# C64_Kernal_Switch.net
KiCad netlist of a schematic drawn in EAGLE
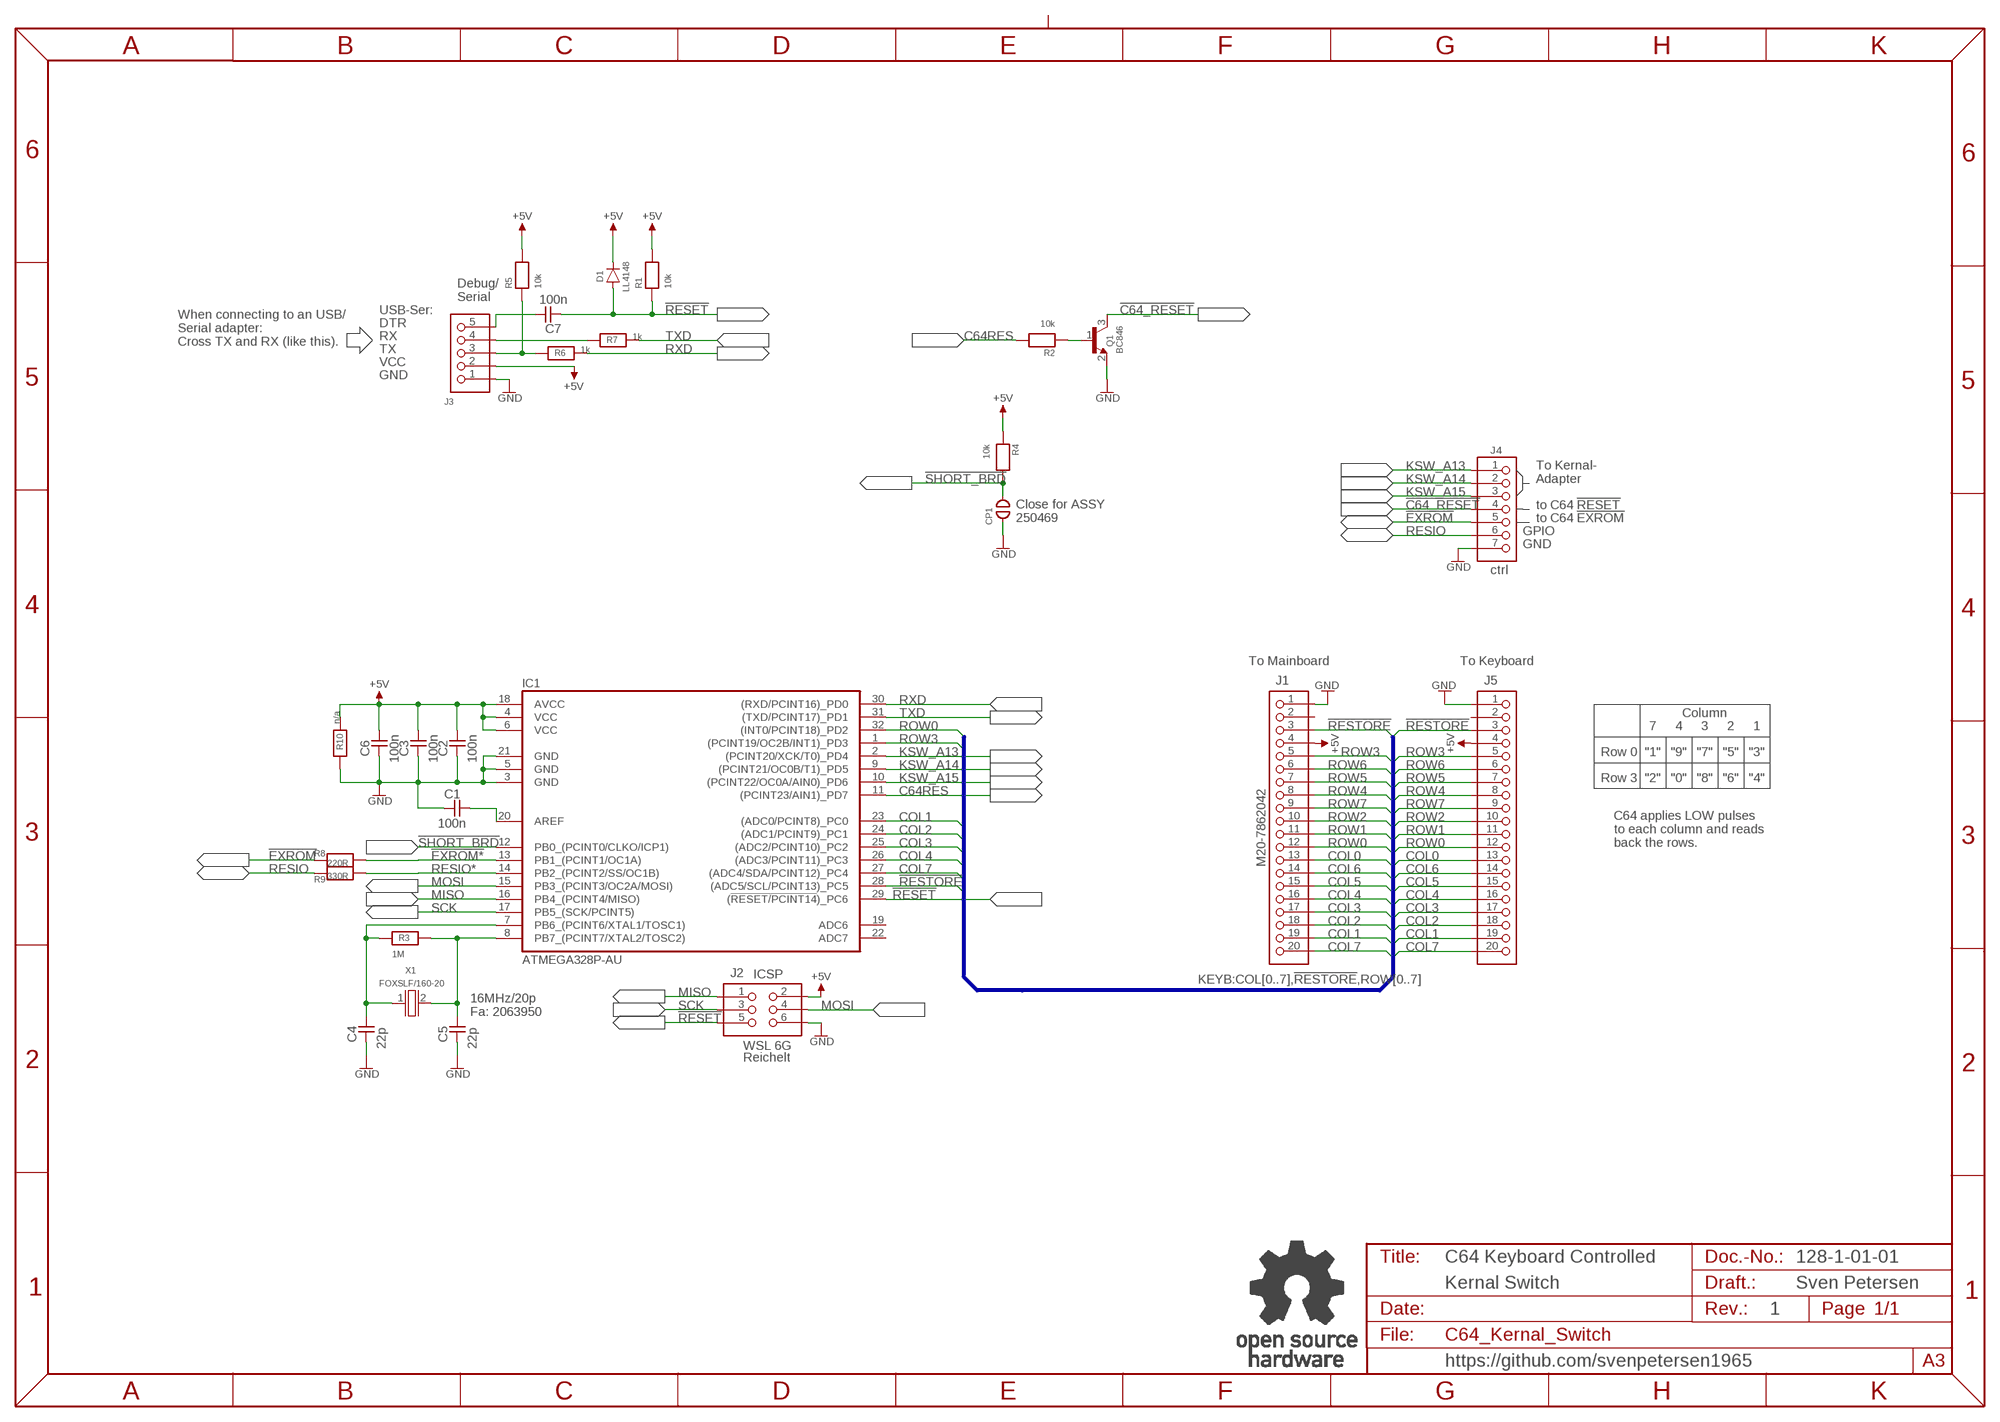
[diagram p0: schematic, sheet 1]

(export (version "E")
  (design (tool "Eeschema 10.0.6"))
  (components
    (comp (ref "C1")
      (value "100n")
      (footprint "eagle-import:0805")
      (libsource (lib "eagle-import") (part "C-0805"))
    )
    (comp (ref "C2")
      (value "100n")
      (footprint "eagle-import:0805")
      (libsource (lib "eagle-import") (part "C-0805"))
    )
    (comp (ref "C3")
      (value "100n")
      (footprint "eagle-import:0805")
      (libsource (lib "eagle-import") (part "C-0805"))
    )
    (comp (ref "C4")
      (value "22p")
      (footprint "eagle-import:0805")
      (libsource (lib "eagle-import") (part "C-0805"))
    )
    (comp (ref "C5")
      (value "22p")
      (footprint "eagle-import:0805")
      (libsource (lib "eagle-import") (part "C-0805"))
    )
    (comp (ref "C6")
      (value "100n")
      (footprint "eagle-import:0805")
      (libsource (lib "eagle-import") (part "C-0805"))
    )
    (comp (ref "C7")
      (value "100n")
      (footprint "eagle-import:0805")
      (libsource (lib "eagle-import") (part "C-0805"))
    )
    (comp (ref "CP1")
      (value "OPEN")
      (footprint "eagle-import:CP_OP")
      (libsource (lib "eagle-import") (part "OPEN"))
    )
    (comp (ref "D1")
      (value "LL4148")
      (footprint "eagle-import:SOD80C")
      (libsource (lib "eagle-import") (part "LL4148"))
    )
    (comp (ref "IC1")
      (value "ATMEGA328P-AU")
      (footprint "eagle-import:QFP80P900X900X120-32N")
      (fields (field (name "MPN") "ATMEGA328-AU"))
      (libsource (lib "eagle-import") (part "ATMEGA328-AU"))
    )
    (comp (ref "J1")
      (value "M20-7862042")
      (footprint "eagle-import:C64_KEYBOARD")
      (fields (field (name "SPICEPREFIX") "X"))
      (libsource (lib "eagle-import") (part "M20-7862042C64KB"))
    )
    (comp (ref "J2")
      (value "WSL 6G")
      (footprint "eagle-import:2X03WV")
      (libsource (lib "eagle-import") (part "2X03WV"))
    )
    (comp (ref "J3")
      (value "n/a")
      (footprint "eagle-import:1X05")
      (libsource (lib "eagle-import") (part "PINHD-1X5"))
    )
    (comp (ref "J4")
      (value "PINHD-1X7")
      (footprint "eagle-import:1X07")
      (libsource (lib "eagle-import") (part "PINHD-1X7"))
    )
    (comp (ref "J5")
      (value "PINHD-1X20")
      (footprint "eagle-import:1X20")
      (libsource (lib "eagle-import") (part "PINHD-1X20"))
    )
    (comp (ref "Q1")
      (value "BC846")
      (footprint "eagle-import:SOT23")
      (libsource (lib "eagle-import") (part "BC846"))
    )
    (comp (ref "R1")
      (value "10k")
      (footprint "eagle-import:0805")
      (libsource (lib "eagle-import") (part "R-0805"))
    )
    (comp (ref "R2")
      (value "10k")
      (footprint "eagle-import:0805")
      (libsource (lib "eagle-import") (part "R-0805"))
    )
    (comp (ref "R3")
      (value "1M")
      (footprint "eagle-import:0805")
      (libsource (lib "eagle-import") (part "R-0805"))
    )
    (comp (ref "R4")
      (value "10k")
      (footprint "eagle-import:0805")
      (libsource (lib "eagle-import") (part "R-0805"))
    )
    (comp (ref "R5")
      (value "10k")
      (footprint "eagle-import:0805")
      (libsource (lib "eagle-import") (part "R-0805"))
    )
    (comp (ref "R6")
      (value "1k")
      (footprint "eagle-import:0805")
      (libsource (lib "eagle-import") (part "R-0805"))
    )
    (comp (ref "R7")
      (value "1k")
      (footprint "eagle-import:0805")
      (libsource (lib "eagle-import") (part "R-0805"))
    )
    (comp (ref "R8")
      (value "220R")
      (footprint "eagle-import:0805")
      (libsource (lib "eagle-import") (part "R-0805"))
    )
    (comp (ref "R9")
      (value "330R")
      (footprint "eagle-import:0805")
      (libsource (lib "eagle-import") (part "R-0805"))
    )
    (comp (ref "R10")
      (value "n/a")
      (footprint "eagle-import:0805")
      (libsource (lib "eagle-import") (part "R-0805"))
    )
    (comp (ref "U$55")
      (value "OPEN_SOURCE_HW")
      (footprint "eagle-import:OPENHW")
      (libsource (lib "eagle-import") (part "OPEN_SOURCE_HW"))
    )
    (comp (ref "X1")
      (value "FOXSLF/160-20")
      (footprint "eagle-import:HC49SLF")
      (libsource (lib "eagle-import") (part "HC49SLF"))
    )
  )
  (nets
    (net (code "1") (name "+5V") (class "Default")
      (node (ref "C2") (pin "2") (pinfunction "2_2") (pintype "passive"))
      (node (ref "C3") (pin "2") (pinfunction "2_2") (pintype "passive"))
      (node (ref "C6") (pin "2") (pinfunction "2_2") (pintype "passive"))
      (node (ref "D1") (pin "K") (pinfunction "K_K") (pintype "passive"))
      (node (ref "IC1") (pin "18") (pinfunction "AVCC_18") (pintype "power_in"))
      (node (ref "IC1") (pin "4") (pinfunction "VCC_4") (pintype "power_in"))
      (node (ref "IC1") (pin "6") (pinfunction "VCC_6") (pintype "power_in"))
      (node (ref "J1") (pin "4") (pinfunction "4_4") (pintype "bidirectional"))
      (node (ref "J2") (pin "2") (pinfunction "2_2") (pintype "passive"))
      (node (ref "J3") (pin "2") (pinfunction "2_2") (pintype "passive"))
      (node (ref "J5") (pin "4") (pinfunction "4_4") (pintype "passive"))
      (node (ref "R1") (pin "2") (pinfunction "2_2") (pintype "passive"))
      (node (ref "R10") (pin "2") (pinfunction "2_2") (pintype "passive"))
      (node (ref "R4") (pin "1") (pinfunction "1_1") (pintype "passive"))
      (node (ref "R5") (pin "2") (pinfunction "2_2") (pintype "passive"))
    )
    (net (code "2") (name "/C64RES") (class "Default")
      (node (ref "IC1") (pin "11") (pinfunction "(PCINT23/AIN1)_PD7_11") (pintype "bidirectional"))
      (node (ref "R2") (pin "2") (pinfunction "2_2") (pintype "passive"))
    )
    (net (code "3") (name "/COL0") (class "Default")
      (node (ref "J1") (pin "13") (pinfunction "13_13") (pintype "bidirectional"))
      (node (ref "J5") (pin "13") (pinfunction "13_13") (pintype "passive"))
    )
    (net (code "4") (name "/COL1") (class "Default")
      (node (ref "IC1") (pin "23") (pinfunction "(ADC0/PCINT8)_PC0_23") (pintype "bidirectional"))
      (node (ref "J1") (pin "19") (pinfunction "19_19") (pintype "bidirectional"))
      (node (ref "J5") (pin "19") (pinfunction "19_19") (pintype "passive"))
    )
    (net (code "5") (name "/COL2") (class "Default")
      (node (ref "IC1") (pin "24") (pinfunction "(ADC1/PCINT9)_PC1_24") (pintype "bidirectional"))
      (node (ref "J1") (pin "18") (pinfunction "18_18") (pintype "bidirectional"))
      (node (ref "J5") (pin "18") (pinfunction "18_18") (pintype "passive"))
    )
    (net (code "6") (name "/COL3") (class "Default")
      (node (ref "IC1") (pin "25") (pinfunction "(ADC2/PCINT10)_PC2_25") (pintype "bidirectional"))
      (node (ref "J1") (pin "17") (pinfunction "17_17") (pintype "bidirectional"))
      (node (ref "J5") (pin "17") (pinfunction "17_17") (pintype "passive"))
    )
    (net (code "7") (name "/COL4") (class "Default")
      (node (ref "IC1") (pin "26") (pinfunction "(ADC3/PCINT11)_PC3_26") (pintype "bidirectional"))
      (node (ref "J1") (pin "16") (pinfunction "16_16") (pintype "bidirectional"))
      (node (ref "J5") (pin "16") (pinfunction "16_16") (pintype "passive"))
    )
    (net (code "8") (name "/COL5") (class "Default")
      (node (ref "J1") (pin "15") (pinfunction "15_15") (pintype "bidirectional"))
      (node (ref "J5") (pin "15") (pinfunction "15_15") (pintype "passive"))
    )
    (net (code "9") (name "/COL6") (class "Default")
      (node (ref "J1") (pin "14") (pinfunction "14_14") (pintype "bidirectional"))
      (node (ref "J5") (pin "14") (pinfunction "14_14") (pintype "passive"))
    )
    (net (code "10") (name "/COL7") (class "Default")
      (node (ref "IC1") (pin "27") (pinfunction "(ADC4/SDA/PCINT12)_PC4_27") (pintype "bidirectional"))
      (node (ref "J1") (pin "20") (pinfunction "20_20") (pintype "bidirectional"))
      (node (ref "J5") (pin "20") (pinfunction "20_20") (pintype "passive"))
    )
    (net (code "11") (name "/KSW_A13") (class "Default")
      (node (ref "IC1") (pin "2") (pinfunction "(PCINT20/XCK/T0)_PD4_2") (pintype "bidirectional"))
      (node (ref "J4") (pin "1") (pinfunction "1_1") (pintype "passive"))
    )
    (net (code "12") (name "/KSW_A14") (class "Default")
      (node (ref "IC1") (pin "9") (pinfunction "(PCINT21/OC0B/T1)_PD5_9") (pintype "bidirectional"))
      (node (ref "J4") (pin "2") (pinfunction "2_2") (pintype "passive"))
    )
    (net (code "13") (name "/KSW_A15") (class "Default")
      (node (ref "IC1") (pin "10") (pinfunction "(PCINT22/OC0A/AIN0)_PD6_10") (pintype "bidirectional"))
      (node (ref "J4") (pin "3") (pinfunction "3_3") (pintype "passive"))
    )
    (net (code "14") (name "/MISO") (class "Default")
      (node (ref "IC1") (pin "16") (pinfunction "PB4_(PCINT4/MISO)_16") (pintype "bidirectional"))
      (node (ref "J2") (pin "1") (pinfunction "1_1") (pintype "passive"))
    )
    (net (code "15") (name "/MOSI") (class "Default")
      (node (ref "IC1") (pin "15") (pinfunction "PB3_(PCINT3/OC2A/MOSI)_15") (pintype "bidirectional"))
      (node (ref "J2") (pin "4") (pinfunction "4_4") (pintype "passive"))
    )
    (net (code "16") (name "/RESIO") (class "Default")
      (node (ref "J4") (pin "6") (pinfunction "6_6") (pintype "passive"))
      (node (ref "R9") (pin "1") (pinfunction "1_1") (pintype "passive"))
    )
    (net (code "17") (name "/RESIO*") (class "Default")
      (node (ref "IC1") (pin "14") (pinfunction "PB2_(PCINT2/SS/OC1B)_14") (pintype "bidirectional"))
      (node (ref "R9") (pin "2") (pinfunction "2_2") (pintype "passive"))
    )
    (net (code "18") (name "/ROW0") (class "Default")
      (node (ref "IC1") (pin "32") (pinfunction "(INT0/PCINT18)_PD2_32") (pintype "bidirectional"))
      (node (ref "J1") (pin "12") (pinfunction "12_12") (pintype "bidirectional"))
      (node (ref "J5") (pin "12") (pinfunction "12_12") (pintype "passive"))
    )
    (net (code "19") (name "/ROW1") (class "Default")
      (node (ref "J1") (pin "11") (pinfunction "11_11") (pintype "bidirectional"))
      (node (ref "J5") (pin "11") (pinfunction "11_11") (pintype "passive"))
    )
    (net (code "20") (name "/ROW2") (class "Default")
      (node (ref "J1") (pin "10") (pinfunction "10_10") (pintype "bidirectional"))
      (node (ref "J5") (pin "10") (pinfunction "10_10") (pintype "passive"))
    )
    (net (code "21") (name "/ROW3") (class "Default")
      (node (ref "IC1") (pin "1") (pinfunction "(PCINT19/OC2B/INT1)_PD3_1") (pintype "bidirectional"))
      (node (ref "J1") (pin "5") (pinfunction "5_5") (pintype "bidirectional"))
      (node (ref "J5") (pin "5") (pinfunction "5_5") (pintype "passive"))
    )
    (net (code "22") (name "/ROW4") (class "Default")
      (node (ref "J1") (pin "8") (pinfunction "8_8") (pintype "bidirectional"))
      (node (ref "J5") (pin "8") (pinfunction "8_8") (pintype "passive"))
    )
    (net (code "23") (name "/ROW5") (class "Default")
      (node (ref "J1") (pin "7") (pinfunction "7_7") (pintype "bidirectional"))
      (node (ref "J5") (pin "7") (pinfunction "7_7") (pintype "passive"))
    )
    (net (code "24") (name "/ROW6") (class "Default")
      (node (ref "J1") (pin "6") (pinfunction "6_6") (pintype "bidirectional"))
      (node (ref "J5") (pin "6") (pinfunction "6_6") (pintype "passive"))
    )
    (net (code "25") (name "/ROW7") (class "Default")
      (node (ref "J1") (pin "9") (pinfunction "9_9") (pintype "bidirectional"))
      (node (ref "J5") (pin "9") (pinfunction "9_9") (pintype "passive"))
    )
    (net (code "26") (name "/RXD") (class "Default")
      (node (ref "IC1") (pin "30") (pinfunction "(RXD/PCINT16)_PD0_30") (pintype "bidirectional"))
      (node (ref "R6") (pin "2") (pinfunction "2_2") (pintype "passive"))
    )
    (net (code "27") (name "/SCK") (class "Default")
      (node (ref "IC1") (pin "17") (pinfunction "PB5_(SCK/PCINT5)_17") (pintype "bidirectional"))
      (node (ref "J2") (pin "3") (pinfunction "3_3") (pintype "passive"))
    )
    (net (code "28") (name "/TXD") (class "Default")
      (node (ref "IC1") (pin "31") (pinfunction "(TXD/PCINT17)_PD1_31") (pintype "bidirectional"))
      (node (ref "R7") (pin "2") (pinfunction "2_2") (pintype "passive"))
    )
    (net (code "30") (name "/~{C64_RESET}") (class "Default")
      (node (ref "J4") (pin "4") (pinfunction "4_4") (pintype "passive"))
      (node (ref "Q1") (pin "3") (pinfunction "C_3") (pintype "passive"))
    )
    (net (code "31") (name "/~{EXROM*}") (class "Default")
      (node (ref "IC1") (pin "13") (pinfunction "PB1_(PCINT1/OC1A)_13") (pintype "bidirectional"))
      (node (ref "R8") (pin "2") (pinfunction "2_2") (pintype "passive"))
    )
    (net (code "32") (name "/~{EXROM}") (class "Default")
      (node (ref "J4") (pin "5") (pinfunction "5_5") (pintype "passive"))
      (node (ref "R8") (pin "1") (pinfunction "1_1") (pintype "passive"))
    )
    (net (code "33") (name "/~{RESET}") (class "Default")
      (node (ref "C7") (pin "1") (pinfunction "1_1") (pintype "passive"))
      (node (ref "D1") (pin "A") (pinfunction "A_A") (pintype "passive"))
      (node (ref "IC1") (pin "29") (pinfunction "(~{RESET/PCINT14})_PC6_29") (pintype "bidirectional"))
      (node (ref "J2") (pin "5") (pinfunction "5_5") (pintype "passive"))
      (node (ref "R1") (pin "1") (pinfunction "1_1") (pintype "passive"))
    )
    (net (code "34") (name "/~{RESTORE}") (class "Default")
      (node (ref "IC1") (pin "28") (pinfunction "(ADC5/SCL/PCINT13)_PC5_28") (pintype "bidirectional"))
      (node (ref "J1") (pin "3") (pinfunction "3_3") (pintype "bidirectional"))
      (node (ref "J5") (pin "3") (pinfunction "3_3") (pintype "passive"))
    )
    (net (code "35") (name "/~{SHORT_BRD}") (class "Default")
      (node (ref "CP1") (pin "2") (pinfunction "2_2") (pintype "passive"))
      (node (ref "IC1") (pin "12") (pinfunction "PB0_(PCINT0/CLKO/ICP1)_12") (pintype "bidirectional"))
      (node (ref "R4") (pin "2") (pinfunction "2_2") (pintype "passive"))
    )
    (net (code "36") (name "GND") (class "Default")
      (node (ref "C1") (pin "1") (pinfunction "1_1") (pintype "passive"))
      (node (ref "C2") (pin "1") (pinfunction "1_1") (pintype "passive"))
      (node (ref "C3") (pin "1") (pinfunction "1_1") (pintype "passive"))
      (node (ref "C4") (pin "1") (pinfunction "1_1") (pintype "passive"))
      (node (ref "C5") (pin "1") (pinfunction "1_1") (pintype "passive"))
      (node (ref "C6") (pin "1") (pinfunction "1_1") (pintype "passive"))
      (node (ref "CP1") (pin "1") (pinfunction "1_1") (pintype "passive"))
      (node (ref "IC1") (pin "21") (pinfunction "GND_21") (pintype "passive"))
      (node (ref "IC1") (pin "3") (pinfunction "GND_3") (pintype "passive"))
      (node (ref "IC1") (pin "5") (pinfunction "GND_5") (pintype "passive"))
      (node (ref "J1") (pin "1") (pinfunction "1_1") (pintype "bidirectional"))
      (node (ref "J2") (pin "6") (pinfunction "6_6") (pintype "passive"))
      (node (ref "J3") (pin "1") (pinfunction "1_1") (pintype "passive"))
      (node (ref "J4") (pin "7") (pinfunction "7_7") (pintype "passive"))
      (node (ref "J5") (pin "1") (pinfunction "1_1") (pintype "passive"))
      (node (ref "Q1") (pin "2") (pinfunction "E_2") (pintype "passive"))
      (node (ref "R10") (pin "1") (pinfunction "1_1") (pintype "passive"))
    )
    (net (code "37") (name "Net-(C7-Pad2)") (class "Default")
      (node (ref "C7") (pin "2") (pinfunction "2_2") (pintype "passive"))
      (node (ref "J3") (pin "5") (pinfunction "5_5") (pintype "passive"))
    )
    (net (code "38") (name "Net-(IC1-AREF)") (class "Default")
      (node (ref "C1") (pin "2") (pinfunction "2_2") (pintype "passive"))
      (node (ref "IC1") (pin "20") (pinfunction "AREF_20") (pintype "passive"))
    )
    (net (code "39") (name "Net-(IC1-PB6_(PCINT6{slash}XTAL1{slash}TOSC1))") (class "Default")
      (node (ref "C4") (pin "2") (pinfunction "2_2") (pintype "passive"))
      (node (ref "IC1") (pin "7") (pinfunction "PB6_(PCINT6/XTAL1/TOSC1)_7") (pintype "bidirectional"))
      (node (ref "R3") (pin "1") (pinfunction "1_1") (pintype "passive"))
      (node (ref "X1") (pin "1") (pinfunction "1_1") (pintype "passive"))
    )
    (net (code "40") (name "Net-(IC1-PB7_(PCINT7{slash}XTAL2{slash}TOSC2))") (class "Default")
      (node (ref "C5") (pin "2") (pinfunction "2_2") (pintype "passive"))
      (node (ref "IC1") (pin "8") (pinfunction "PB7_(PCINT7/XTAL2/TOSC2)_8") (pintype "bidirectional"))
      (node (ref "R3") (pin "2") (pinfunction "2_2") (pintype "passive"))
      (node (ref "X1") (pin "2") (pinfunction "2_2") (pintype "passive"))
    )
    (net (code "41") (name "Net-(J3-Pad3)") (class "Default")
      (node (ref "J3") (pin "3") (pinfunction "3_3") (pintype "passive"))
      (node (ref "R5") (pin "1") (pinfunction "1_1") (pintype "passive"))
      (node (ref "R6") (pin "1") (pinfunction "1_1") (pintype "passive"))
    )
    (net (code "42") (name "Net-(J3-Pad4)") (class "Default")
      (node (ref "J3") (pin "4") (pinfunction "4_4") (pintype "passive"))
      (node (ref "R7") (pin "1") (pinfunction "1_1") (pintype "passive"))
    )
    (net (code "43") (name "Net-(Q1-B)") (class "Default")
      (node (ref "Q1") (pin "1") (pinfunction "B_1") (pintype "passive"))
      (node (ref "R2") (pin "1") (pinfunction "1_1") (pintype "passive"))
    )
    (net (code "44") (name "unconnected-(IC1-ADC6-Pad19)") (class "Default")
      (node (ref "IC1") (pin "19") (pinfunction "ADC6_19") (pintype "input"))
    )
    (net (code "45") (name "unconnected-(IC1-ADC7-Pad22)") (class "Default")
      (node (ref "IC1") (pin "22") (pinfunction "ADC7_22") (pintype "input"))
    )
    (net (code "46") (name "unconnected-(J1-Pad2)") (class "Default")
      (node (ref "J1") (pin "2") (pinfunction "2_2") (pintype "bidirectional"))
    )
    (net (code "47") (name "unconnected-(J5-Pad2)") (class "Default")
      (node (ref "J5") (pin "2") (pinfunction "2_2") (pintype "passive"))
    )
  )
)
